# design.net
KiCad netlist of a schematic drawn in Altium Designer
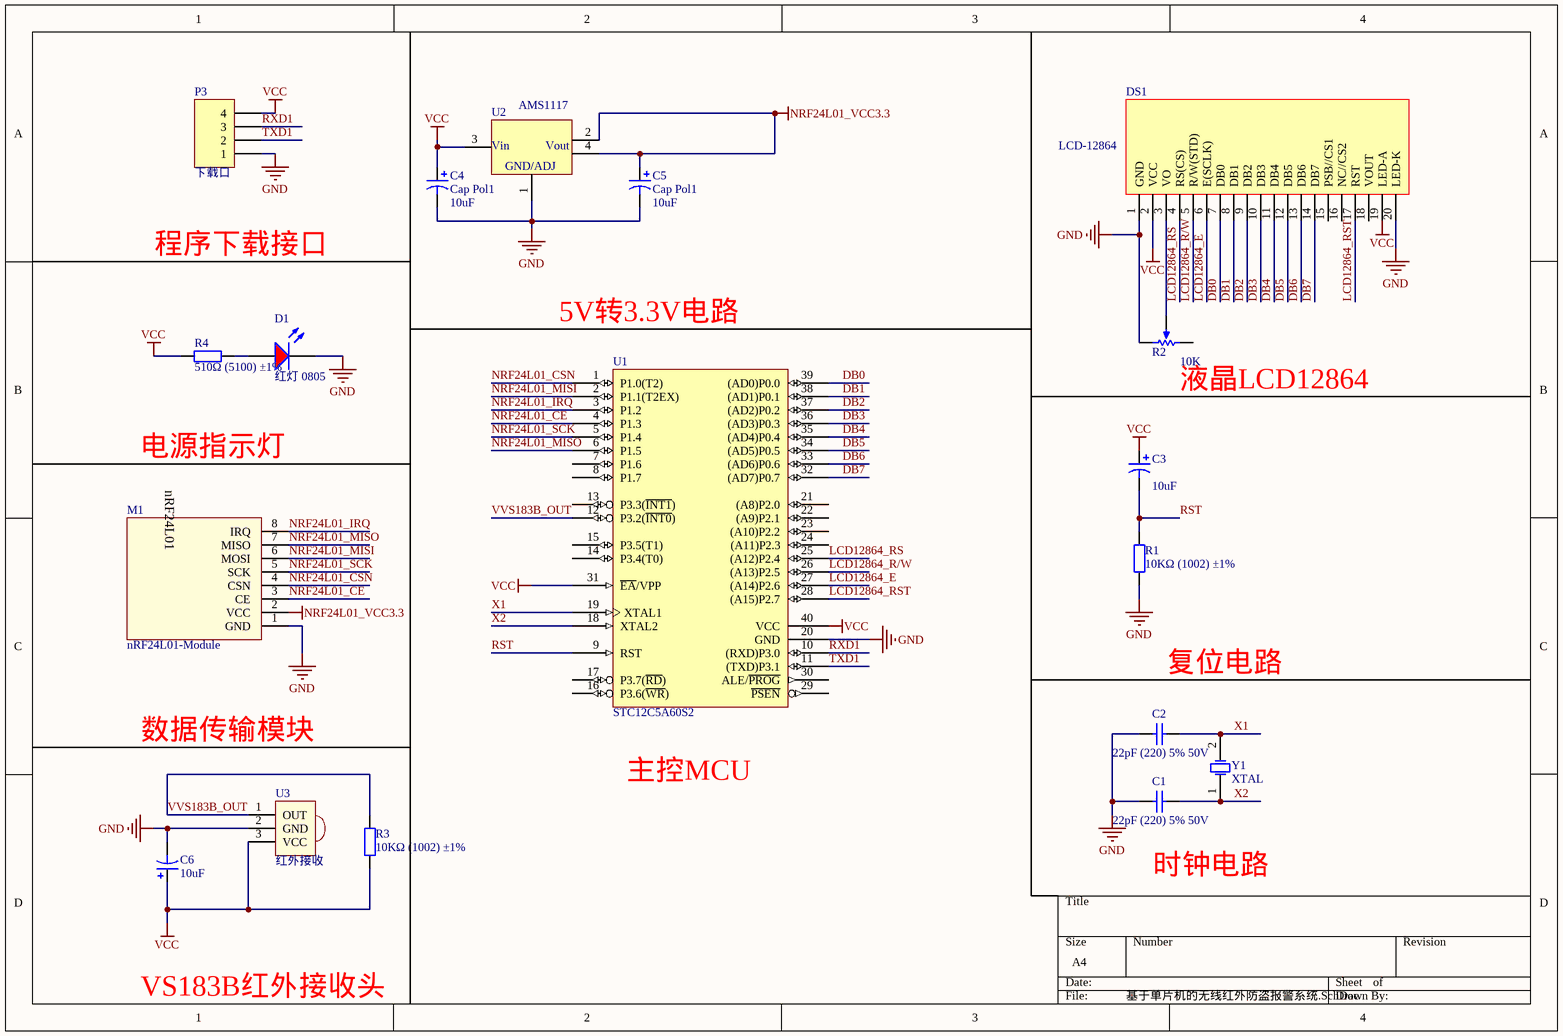
[diagram p0: 基于单片机的无线红外防盗报警系统.SchDoc]

(export (version "E")
  (design (tool "Eeschema 10.0.6"))
  (components
    (comp (ref "C1")
      (value "22pF (220) 5% 50V")
      (footprint "LC-0805_C")
      (description "贴片电容")
      (libsource (lib "Miscellaneous Devices LC") (part "0805 22pF (220) 5% 50V"))
    )
    (comp (ref "C2")
      (value "22pF (220) 5% 50V")
      (footprint "LC-0805_C")
      (description "贴片电容")
      (libsource (lib "Miscellaneous Devices LC") (part "0805 22pF (220) 5% 50V"))
    )
    (comp (ref "C3")
      (value "10uF")
      (footprint "RB.2.5/.6.3mm")
      (description "Polarized Capacitor (Radial)")
      (fields (field (name "Comment") "Cap Pol1") (field (name "PUBLISHER") "Altium Limited"))
      (libsource (lib "Miscellaneous Devices") (part "Cap Pol1"))
    )
    (comp (ref "C4")
      (value "Cap Pol1")
      (footprint "RB.2.5/.6.3mm")
      (description "Polarized Capacitor (Radial)")
      (fields (field (name "ALTIUM_VALUE") "10uF") (field (name "PUBLISHER") "Altium Limited"))
      (libsource (lib "Miscellaneous Devices") (part "Cap Pol1"))
    )
    (comp (ref "C5")
      (value "Cap Pol1")
      (footprint "RB.2.5/.6.3mm")
      (description "Polarized Capacitor (Radial)")
      (fields (field (name "ALTIUM_VALUE") "10uF") (field (name "PUBLISHER") "Altium Limited"))
      (libsource (lib "Miscellaneous Devices") (part "Cap Pol1"))
    )
    (comp (ref "C6")
      (value "10uF")
      (footprint "RB.2.5/.6.3mm")
      (description "Polarized Capacitor (Radial)")
      (fields (field (name "Comment") "Cap Pol1") (field (name "PUBLISHER") "Altium Limited"))
      (libsource (lib "Miscellaneous Devices") (part "Cap Pol1"))
    )
    (comp (ref "D1")
      (value "红灯 0805")
      (footprint "LC-0805_LED_S1")
      (description "发光二极管")
      (libsource (lib "Miscellaneous Devices LC") (part "0805 红灯"))
    )
    (comp (ref "DS1")
      (value "LCD-12864")
      (footprint "LCD-12864")
      (description "带//不带字库")
      (libsource (lib "个人") (part "LCD-12864"))
    )
    (comp (ref "M1")
      (value "nRF24L01-Module")
      (footprint "HDR2X4")
      (libsource (lib "个人") (part "nRF24L01-Module"))
    )
    (comp (ref "P3")
      (value "下载口")
      (footprint "HDR1X4")
      (description "Header, 4-Pin")
      (fields (field (name "PUBLISHER") "Altium Limited"))
      (libsource (lib "Miscellaneous Connectors") (part "Header 4"))
    )
    (comp (ref "R1")
      (value "10KΩ (1002) ±1%")
      (footprint "LC-0805_R")
      (description "贴片电阻")
      (libsource (lib "Miscellaneous Devices LC") (part "0805 10KΩ (1002) 1%"))
    )
    (comp (ref "R2")
      (value "10K")
      (footprint "VR5")
      (description "Potentiometer")
      (fields (field (name "Comment") "Pot") (field (name "PUBLISHER") "Altium Limited"))
      (libsource (lib "Miscellaneous Devices") (part "RPot"))
    )
    (comp (ref "R3")
      (value "10KΩ (1002) ±1%")
      (footprint "LC-0805_R")
      (description "贴片电阻")
      (libsource (lib "Miscellaneous Devices LC") (part "0805 10KΩ (1002) 1%"))
    )
    (comp (ref "R4")
      (value "510Ω (5100) ±1%")
      (footprint "LC-0805_R")
      (description "贴片电阻")
      (libsource (lib "Miscellaneous Devices LC") (part "0805 510Ω (5100) 1%"))
    )
    (comp (ref "U1")
      (value "STC12C5A60S2")
      (footprint "DIP40")
      (description "8-Bit Microcontroller with 8K Flash ROM")
      (libsource (lib "Atmel Microcontroller 8051 Architecture") (part "AT89C52"))
    )
    (comp (ref "U2") (value "AMS1117") (footprint "LC-SOT-223") (libsource (lib "个人") (part "AMS1117")))
    (comp (ref "U3")
      (value "红外接收")
      (footprint "HDR1X3")
      (description "VS838")
      (libsource (lib "个人") (part "红外接收"))
    )
    (comp (ref "Y1")
      (value "XTAL")
      (footprint "R38")
      (description "Crystal Oscillator")
      (fields (field (name "PUBLISHER") "Altium Limited"))
      (libsource (lib "Miscellaneous Devices") (part "XTAL"))
    )
  )
  (nets
    (net (code "1") (name "/DB0") (class "Default")
      (node (ref "DS1") (pin "7") (pinfunction "DB0_7") (pintype "passive"))
      (node (ref "U1") (pin "39") (pinfunction "(AD0)P0.0_39") (pintype "bidirectional"))
    )
    (net (code "2") (name "/DB1") (class "Default")
      (node (ref "DS1") (pin "8") (pinfunction "DB1_8") (pintype "passive"))
      (node (ref "U1") (pin "38") (pinfunction "(AD1)P0.1_38") (pintype "bidirectional"))
    )
    (net (code "3") (name "/DB2") (class "Default")
      (node (ref "DS1") (pin "9") (pinfunction "DB2_9") (pintype "passive"))
      (node (ref "U1") (pin "37") (pinfunction "(AD2)P0.2_37") (pintype "bidirectional"))
    )
    (net (code "4") (name "/DB3") (class "Default")
      (node (ref "DS1") (pin "10") (pinfunction "DB3_10") (pintype "passive"))
      (node (ref "U1") (pin "36") (pinfunction "(AD3)P0.3_36") (pintype "bidirectional"))
    )
    (net (code "5") (name "/DB4") (class "Default")
      (node (ref "DS1") (pin "11") (pinfunction "DB4_11") (pintype "passive"))
      (node (ref "U1") (pin "35") (pinfunction "(AD4)P0.4_35") (pintype "bidirectional"))
    )
    (net (code "6") (name "/DB5") (class "Default")
      (node (ref "DS1") (pin "12") (pinfunction "DB5_12") (pintype "passive"))
      (node (ref "U1") (pin "34") (pinfunction "(AD5)P0.5_34") (pintype "bidirectional"))
    )
    (net (code "7") (name "/DB6") (class "Default")
      (node (ref "DS1") (pin "13") (pinfunction "DB6_13") (pintype "passive"))
      (node (ref "U1") (pin "33") (pinfunction "(AD6)P0.6_33") (pintype "bidirectional"))
    )
    (net (code "8") (name "/DB7") (class "Default")
      (node (ref "DS1") (pin "14") (pinfunction "DB7_14") (pintype "passive"))
      (node (ref "U1") (pin "32") (pinfunction "(AD7)P0.7_32") (pintype "bidirectional"))
    )
    (net (code "9") (name "/LCD12864_E") (class "Default")
      (node (ref "DS1") (pin "6") (pinfunction "E(SCLK)_6") (pintype "passive"))
      (node (ref "U1") (pin "27") (pinfunction "(A14)P2.6_27") (pintype "bidirectional"))
    )
    (net (code "10") (name "/LCD12864_RS") (class "Default")
      (node (ref "DS1") (pin "4") (pinfunction "RS(CS)_4") (pintype "passive"))
      (node (ref "U1") (pin "25") (pinfunction "(A12)P2.4_25") (pintype "bidirectional"))
    )
    (net (code "11") (name "/LCD12864_RST") (class "Default")
      (node (ref "DS1") (pin "17") (pinfunction "RST_17") (pintype "passive"))
      (node (ref "U1") (pin "28") (pinfunction "(A15)P2.7_28") (pintype "bidirectional"))
    )
    (net (code "12") (name "/LCD12864_R{slash}W") (class "Default")
      (node (ref "DS1") (pin "5") (pinfunction "R/W(STD)_5") (pintype "passive"))
      (node (ref "U1") (pin "26") (pinfunction "(A13)P2.5_26") (pintype "bidirectional"))
    )
    (net (code "13") (name "/NRF24L01_CE") (class "Default")
      (node (ref "M1") (pin "3") (pinfunction "CE_3") (pintype "passive"))
      (node (ref "U1") (pin "4") (pinfunction "P1.3_4") (pintype "bidirectional"))
    )
    (net (code "14") (name "/NRF24L01_CSN") (class "Default")
      (node (ref "M1") (pin "4") (pinfunction "CSN_4") (pintype "passive"))
      (node (ref "U1") (pin "1") (pinfunction "P1.0(T2)_1") (pintype "bidirectional"))
    )
    (net (code "15") (name "/NRF24L01_IRQ") (class "Default")
      (node (ref "M1") (pin "8") (pinfunction "IRQ_8") (pintype "passive"))
      (node (ref "U1") (pin "3") (pinfunction "P1.2_3") (pintype "bidirectional"))
    )
    (net (code "16") (name "/NRF24L01_MISI") (class "Default")
      (node (ref "M1") (pin "6") (pinfunction "MOSI_6") (pintype "passive"))
      (node (ref "U1") (pin "2") (pinfunction "P1.1(T2EX)_2") (pintype "bidirectional"))
    )
    (net (code "17") (name "/NRF24L01_MISO") (class "Default")
      (node (ref "M1") (pin "7") (pinfunction "MISO_7") (pintype "passive"))
      (node (ref "U1") (pin "6") (pinfunction "P1.5_6") (pintype "bidirectional"))
    )
    (net (code "18") (name "/NRF24L01_SCK") (class "Default")
      (node (ref "M1") (pin "5") (pinfunction "SCK_5") (pintype "passive"))
      (node (ref "U1") (pin "5") (pinfunction "P1.4_5") (pintype "bidirectional"))
    )
    (net (code "19") (name "/RST") (class "Default")
      (node (ref "C3") (pin "2") (pinfunction "2_2") (pintype "passive"))
      (node (ref "R1") (pin "2") (pinfunction "2_2") (pintype "passive"))
      (node (ref "U1") (pin "9") (pinfunction "RST_9") (pintype "input"))
    )
    (net (code "20") (name "/RXD1") (class "Default")
      (node (ref "P3") (pin "3") (pinfunction "3_3") (pintype "passive"))
      (node (ref "U1") (pin "10") (pinfunction "(RXD)P3.0_10") (pintype "bidirectional"))
    )
    (net (code "21") (name "/TXD1") (class "Default")
      (node (ref "P3") (pin "2") (pinfunction "2_2") (pintype "passive"))
      (node (ref "U1") (pin "11") (pinfunction "(TXD)P3.1_11") (pintype "bidirectional"))
    )
    (net (code "22") (name "/VVS183B_OUT") (class "Default")
      (node (ref "R3") (pin "2") (pinfunction "2_2") (pintype "passive"))
      (node (ref "U1") (pin "12") (pinfunction "P3.2(~{INT0})_12") (pintype "bidirectional"))
      (node (ref "U3") (pin "1") (pinfunction "OUT_1") (pintype "passive"))
    )
    (net (code "23") (name "/X1") (class "Default")
      (node (ref "C2") (pin "2") (pinfunction "2_2") (pintype "passive"))
      (node (ref "U1") (pin "19") (pinfunction "XTAL1_19") (pintype "input"))
      (node (ref "Y1") (pin "2") (pinfunction "OSC2_2") (pintype "passive"))
    )
    (net (code "24") (name "/X2") (class "Default")
      (node (ref "C1") (pin "2") (pinfunction "2_2") (pintype "passive"))
      (node (ref "U1") (pin "18") (pinfunction "XTAL2_18") (pintype "input"))
      (node (ref "Y1") (pin "1") (pinfunction "OSC1_1") (pintype "passive"))
    )
    (net (code "25") (name "GND") (class "Default")
      (node (ref "C1") (pin "1") (pinfunction "1_1") (pintype "passive"))
      (node (ref "C2") (pin "1") (pinfunction "1_1") (pintype "passive"))
      (node (ref "C4") (pin "2") (pinfunction "2_2") (pintype "passive"))
      (node (ref "C5") (pin "2") (pinfunction "2_2") (pintype "passive"))
      (node (ref "C6") (pin "2") (pinfunction "2_2") (pintype "passive"))
      (node (ref "D1") (pin "K") (pinfunction "K_K") (pintype "passive"))
      (node (ref "DS1") (pin "1") (pinfunction "GND_1") (pintype "passive"))
      (node (ref "DS1") (pin "20") (pinfunction "LED-K_20") (pintype "passive"))
      (node (ref "M1") (pin "1") (pinfunction "GND_1") (pintype "passive"))
      (node (ref "P3") (pin "1") (pinfunction "1_1") (pintype "passive"))
      (node (ref "R1") (pin "1") (pinfunction "1_1") (pintype "passive"))
      (node (ref "R2") (pin "2") (pinfunction "BOT_2") (pintype "passive"))
      (node (ref "U1") (pin "20") (pinfunction "GND_20") (pintype "power_in"))
      (node (ref "U2") (pin "1") (pintype "passive"))
      (node (ref "U3") (pin "2") (pinfunction "GND_2") (pintype "passive"))
    )
    (net (code "26") (name "NRF24L01_VCC3.3") (class "Default")
      (node (ref "C5") (pin "1") (pinfunction "1_1") (pintype "passive"))
      (node (ref "M1") (pin "2") (pinfunction "VCC_2") (pintype "passive"))
      (node (ref "U2") (pin "2") (pintype "passive"))
      (node (ref "U2") (pin "4") (pintype "passive"))
    )
    (net (code "27") (name "Net-(D1-PadA)") (class "Default")
      (node (ref "D1") (pin "A") (pinfunction "A_A") (pintype "passive"))
      (node (ref "R4") (pin "2") (pinfunction "2_2") (pintype "passive"))
    )
    (net (code "28") (name "Net-(DS1-VO)") (class "Default")
      (node (ref "DS1") (pin "3") (pinfunction "VO_3") (pintype "passive"))
      (node (ref "R2") (pin "3") (pinfunction "TAP_3") (pintype "passive"))
    )
    (net (code "29") (name "VCC") (class "Default")
      (node (ref "C3") (pin "1") (pinfunction "1_1") (pintype "passive"))
      (node (ref "C4") (pin "1") (pinfunction "1_1") (pintype "passive"))
      (node (ref "C6") (pin "1") (pinfunction "1_1") (pintype "passive"))
      (node (ref "DS1") (pin "19") (pinfunction "LED-A_19") (pintype "passive"))
      (node (ref "DS1") (pin "2") (pinfunction "VCC_2") (pintype "passive"))
      (node (ref "P3") (pin "4") (pinfunction "4_4") (pintype "passive"))
      (node (ref "R3") (pin "1") (pinfunction "1_1") (pintype "passive"))
      (node (ref "R4") (pin "1") (pinfunction "1_1") (pintype "passive"))
      (node (ref "U1") (pin "31") (pinfunction "~{EA}/VPP_31") (pintype "input"))
      (node (ref "U1") (pin "40") (pinfunction "VCC_40") (pintype "power_in"))
      (node (ref "U2") (pin "3") (pintype "passive"))
      (node (ref "U3") (pin "3") (pinfunction "VCC_3") (pintype "passive"))
    )
    (net (code "30") (name "unconnected-(DS1-NC{slash}{slash}CS2-Pad16)") (class "Default")
      (node (ref "DS1") (pin "16") (pinfunction "NC//CS2_16") (pintype "passive"))
    )
    (net (code "31") (name "unconnected-(DS1-PSB{slash}{slash}CS1-Pad15)") (class "Default")
      (node (ref "DS1") (pin "15") (pinfunction "PSB//CS1_15") (pintype "passive"))
    )
    (net (code "32") (name "unconnected-(DS1-VOUT-Pad18)") (class "Default")
      (node (ref "DS1") (pin "18") (pinfunction "VOUT_18") (pintype "passive"))
    )
    (net (code "33") (name "unconnected-(R2-TOP-Pad1)") (class "Default")
      (node (ref "R2") (pin "1") (pinfunction "TOP_1") (pintype "passive"))
    )
    (net (code "34") (name "unconnected-(U1-(A8)P2.0-Pad21)") (class "Default")
      (node (ref "U1") (pin "21") (pinfunction "(A8)P2.0_21") (pintype "bidirectional"))
    )
    (net (code "35") (name "unconnected-(U1-(A9)P2.1-Pad22)") (class "Default")
      (node (ref "U1") (pin "22") (pinfunction "(A9)P2.1_22") (pintype "bidirectional"))
    )
    (net (code "36") (name "unconnected-(U1-(A10)P2.2-Pad23)") (class "Default")
      (node (ref "U1") (pin "23") (pinfunction "(A10)P2.2_23") (pintype "bidirectional"))
    )
    (net (code "37") (name "unconnected-(U1-(A11)P2.3-Pad24)") (class "Default")
      (node (ref "U1") (pin "24") (pinfunction "(A11)P2.3_24") (pintype "bidirectional"))
    )
    (net (code "38") (name "unconnected-(U1-ALE{slash}~{PROG}-Pad30)") (class "Default")
      (node (ref "U1") (pin "30") (pinfunction "ALE/~{PROG}_30") (pintype "output"))
    )
    (net (code "39") (name "unconnected-(U1-P1.6-Pad7)") (class "Default")
      (node (ref "U1") (pin "7") (pinfunction "P1.6_7") (pintype "bidirectional"))
    )
    (net (code "40") (name "unconnected-(U1-P1.7-Pad8)") (class "Default")
      (node (ref "U1") (pin "8") (pinfunction "P1.7_8") (pintype "bidirectional"))
    )
    (net (code "41") (name "unconnected-(U1-P3.3(~{INT1})-Pad13)") (class "Default")
      (node (ref "U1") (pin "13") (pinfunction "P3.3(~{INT1})_13") (pintype "bidirectional"))
    )
    (net (code "42") (name "unconnected-(U1-P3.4(T0)-Pad14)") (class "Default")
      (node (ref "U1") (pin "14") (pinfunction "P3.4(T0)_14") (pintype "bidirectional"))
    )
    (net (code "43") (name "unconnected-(U1-P3.5(T1)-Pad15)") (class "Default")
      (node (ref "U1") (pin "15") (pinfunction "P3.5(T1)_15") (pintype "bidirectional"))
    )
    (net (code "44") (name "unconnected-(U1-P3.6(~{WR})-Pad16)") (class "Default")
      (node (ref "U1") (pin "16") (pinfunction "P3.6(~{WR})_16") (pintype "bidirectional"))
    )
    (net (code "45") (name "unconnected-(U1-P3.7(~{RD})-Pad17)") (class "Default")
      (node (ref "U1") (pin "17") (pinfunction "P3.7(~{RD})_17") (pintype "bidirectional"))
    )
    (net (code "46") (name "unconnected-(U1-~{PSEN}-Pad29)") (class "Default")
      (node (ref "U1") (pin "29") (pinfunction "~{PSEN}_29") (pintype "output"))
    )
  )
)
